# SOM_POWER.net
KiCad netlist of a schematic drawn in Altium Designer
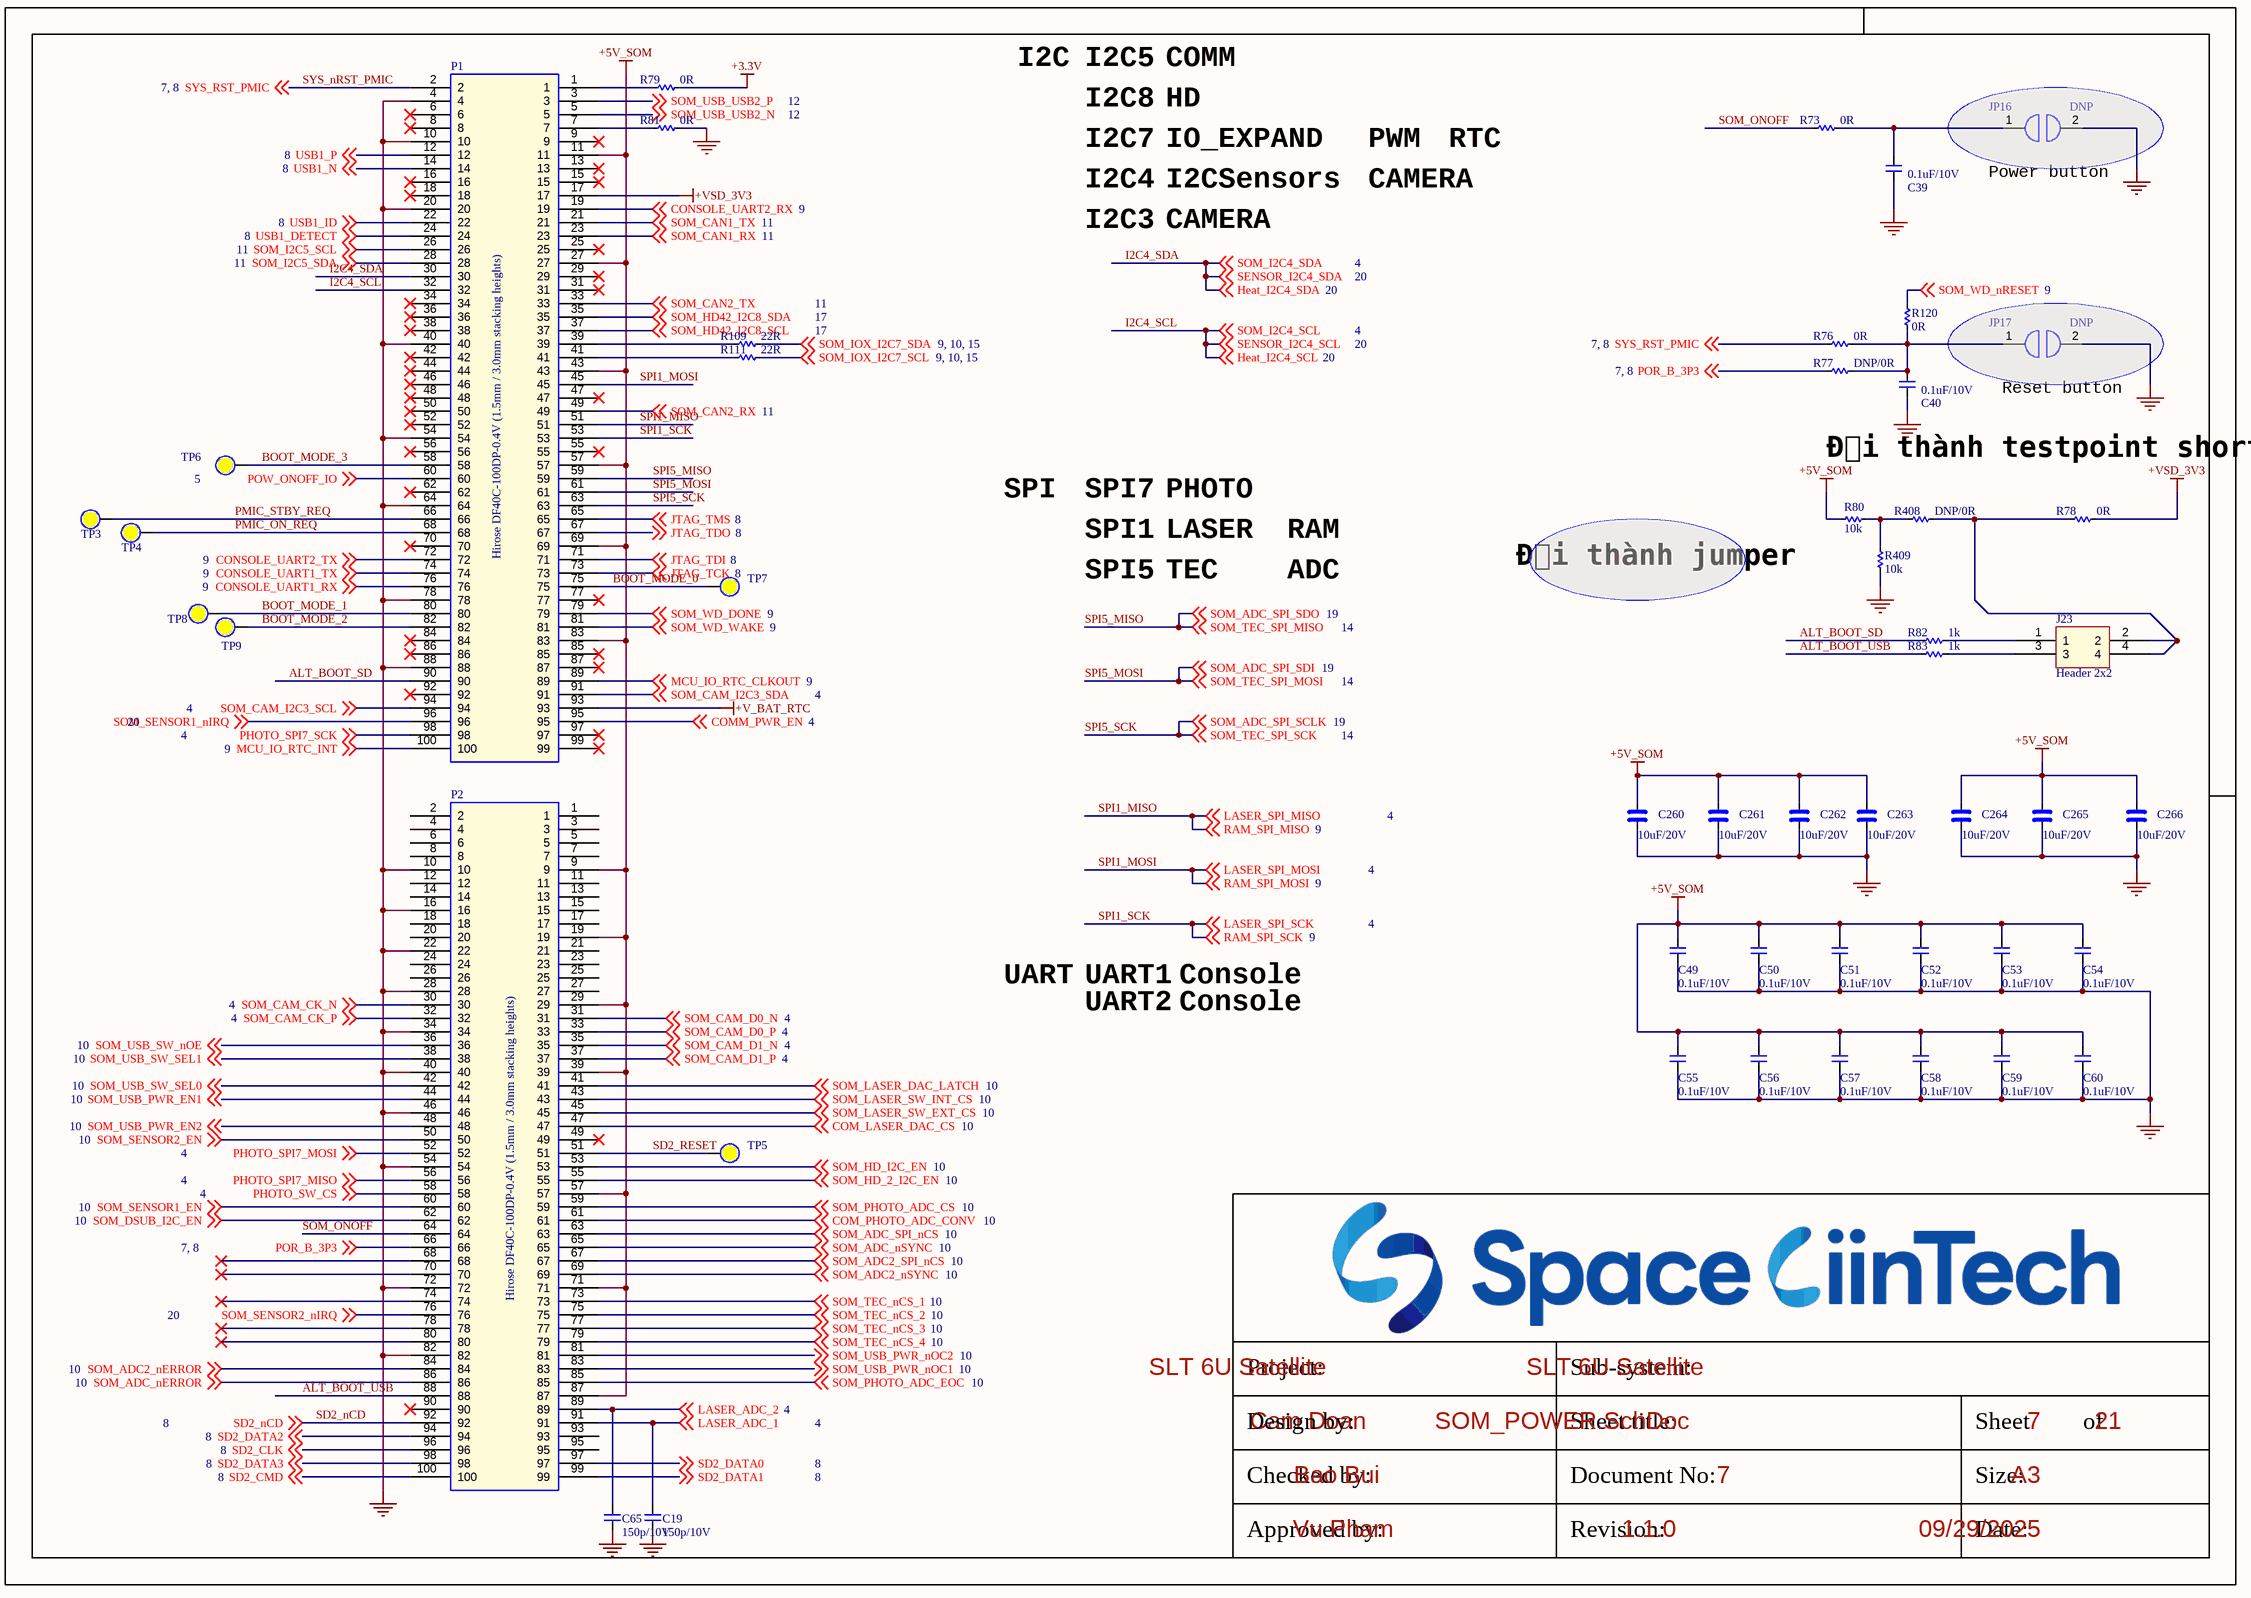
[diagram p0: SOM_POWER.SchDoc]

(export (version "E")
  (design (tool "Eeschema 10.0.6"))
  (components
    (comp (ref "C19")
      (value "150p/10V")
      (footprint "CAP_C_1005X60")
      (description "CAP CHIP")
      (libsource (lib "LABLIB") (part "_CAP_C_2"))
    )
    (comp (ref "C39")
      (value "0.1uF/10V")
      (footprint "CAP_C_1005X60")
      (description "CAP CHIP")
      (libsource (lib "LABLIB") (part "_CAP_C_2"))
    )
    (comp (ref "C40")
      (value "0.1uF/10V")
      (footprint "CAP_C_1005X60")
      (description "CAP CHIP")
      (libsource (lib "LABLIB") (part "_CAP_C_2"))
    )
    (comp (ref "C49")
      (value "0.1uF/10V")
      (footprint "CAP_C_1005X60")
      (description "CAP CHIP")
      (libsource (lib "LABLIB") (part "_CAP_C_2"))
    )
    (comp (ref "C50")
      (value "0.1uF/10V")
      (footprint "CAP_C_1005X60")
      (description "CAP CHIP")
      (libsource (lib "LABLIB") (part "_CAP_C_2"))
    )
    (comp (ref "C51")
      (value "0.1uF/10V")
      (footprint "CAP_C_1005X60")
      (description "CAP CHIP")
      (libsource (lib "LABLIB") (part "_CAP_C_2"))
    )
    (comp (ref "C52")
      (value "0.1uF/10V")
      (footprint "CAP_C_1005X60")
      (description "CAP CHIP")
      (libsource (lib "LABLIB") (part "_CAP_C_2"))
    )
    (comp (ref "C53")
      (value "0.1uF/10V")
      (footprint "CAP_C_1005X60")
      (description "CAP CHIP")
      (libsource (lib "LABLIB") (part "_CAP_C_2"))
    )
    (comp (ref "C54")
      (value "0.1uF/10V")
      (footprint "CAP_C_1005X60")
      (description "CAP CHIP")
      (libsource (lib "LABLIB") (part "_CAP_C_2"))
    )
    (comp (ref "C55")
      (value "0.1uF/10V")
      (footprint "CAP_C_1005X60")
      (description "CAP CHIP")
      (libsource (lib "LABLIB") (part "_CAP_C_2"))
    )
    (comp (ref "C56")
      (value "0.1uF/10V")
      (footprint "CAP_C_1005X60")
      (description "CAP CHIP")
      (libsource (lib "LABLIB") (part "_CAP_C_2"))
    )
    (comp (ref "C57")
      (value "0.1uF/10V")
      (footprint "CAP_C_1005X60")
      (description "CAP CHIP")
      (libsource (lib "LABLIB") (part "_CAP_C_2"))
    )
    (comp (ref "C58")
      (value "0.1uF/10V")
      (footprint "CAP_C_1005X60")
      (description "CAP CHIP")
      (libsource (lib "LABLIB") (part "_CAP_C_2"))
    )
    (comp (ref "C59")
      (value "0.1uF/10V")
      (footprint "CAP_C_1005X60")
      (description "CAP CHIP")
      (libsource (lib "LABLIB") (part "_CAP_C_2"))
    )
    (comp (ref "C60")
      (value "0.1uF/10V")
      (footprint "CAP_C_1005X60")
      (description "CAP CHIP")
      (libsource (lib "LABLIB") (part "_CAP_C_2"))
    )
    (comp (ref "C65")
      (value "150p/10V")
      (footprint "CAP_C_1005X60")
      (description "CAP CHIP")
      (libsource (lib "LABLIB") (part "_CAP_C_2"))
    )
    (comp (ref "C260")
      (value "10uF/20V")
      (footprint "CAP_C_2012X110")
      (description "CAP CHIP High Value")
      (libsource (lib "LABLIB") (part "_CAP_C_High_2"))
    )
    (comp (ref "C261")
      (value "10uF/20V")
      (footprint "CAP_C_2012X110")
      (description "CAP CHIP High Value")
      (libsource (lib "LABLIB") (part "_CAP_C_High_2"))
    )
    (comp (ref "C262")
      (value "10uF/20V")
      (footprint "CAP_C_2012X110")
      (description "CAP CHIP High Value")
      (libsource (lib "LABLIB") (part "_CAP_C_High_2"))
    )
    (comp (ref "C263")
      (value "10uF/20V")
      (footprint "CAP_C_2012X110")
      (description "CAP CHIP High Value")
      (libsource (lib "LABLIB") (part "_CAP_C_High_2"))
    )
    (comp (ref "C264")
      (value "10uF/20V")
      (footprint "CAP_C_2012X110")
      (description "CAP CHIP High Value")
      (libsource (lib "LABLIB") (part "_CAP_C_High_2"))
    )
    (comp (ref "C265")
      (value "10uF/20V")
      (footprint "CAP_C_2012X110")
      (description "CAP CHIP High Value")
      (libsource (lib "LABLIB") (part "_CAP_C_High_2"))
    )
    (comp (ref "C266")
      (value "10uF/20V")
      (footprint "CAP_C_2012X110")
      (description "CAP CHIP High Value")
      (libsource (lib "LABLIB") (part "_CAP_C_High_2"))
    )
    (comp (ref "J23")
      (value "Header 2x2")
      (footprint "CONN_54202-T0802ALF")
      (libsource (lib "LABLIB") (part "Header 2x2_Z"))
    )
    (comp (ref "JP16")
      (value "DNP")
      (footprint "TESTPOINT_SHORT_120X100_60")
      (libsource (lib "EXP_V1") (part "JUMPER"))
    )
    (comp (ref "JP17")
      (value "DNP")
      (footprint "TESTPOINT_SHORT_120X100_60")
      (libsource (lib "EXP_V1") (part "JUMPER"))
    )
    (comp (ref "P1")
      (value "Hirose DF40C-100DP-0.4V (1.5mm / 3.0mm stacking heights)")
      (footprint "B2B04M2X50R")
      (libsource (lib "*") (part "Hirose DF40C-100DP-0_0.4V"))
    )
    (comp (ref "P2")
      (value "Hirose DF40C-100DP-0.4V (1.5mm / 3.0mm stacking heights)")
      (footprint "B2B04M2X50R")
      (libsource (lib "*") (part "Hirose DF40C-100DP-0_1.4V"))
    )
    (comp (ref "R73")
      (value "0R")
      (footprint "RES_C_1005X40")
      (description "RES")
      (libsource (lib "LABLIB") (part "_RES_B_2"))
    )
    (comp (ref "R76")
      (value "0R")
      (footprint "RES_C_1005X40")
      (description "RES")
      (libsource (lib "LABLIB") (part "_RES_B_2"))
    )
    (comp (ref "R77")
      (value "DNP/0R")
      (footprint "RES_C_1005X40")
      (description "RES")
      (libsource (lib "LABLIB") (part "_RES_B_2"))
    )
    (comp (ref "R78")
      (value "0R")
      (footprint "RES_C_1005X40")
      (description "RES")
      (libsource (lib "LABLIB") (part "_RES_B_2"))
    )
    (comp (ref "R79")
      (value "0R")
      (footprint "RES_C_1005X40")
      (description "RES")
      (libsource (lib "LABLIB") (part "_RES_B_2"))
    )
    (comp (ref "R80")
      (value "10k")
      (footprint "RES_C_1005X40")
      (description "RES")
      (libsource (lib "LABLIB") (part "_RES_B_2"))
    )
    (comp (ref "R81")
      (value "0R")
      (footprint "RES_C_1005X40")
      (description "RES")
      (libsource (lib "LABLIB") (part "_RES_B_2"))
    )
    (comp (ref "R82")
      (value "1k")
      (footprint "RES_C_1005X40")
      (description "RES")
      (libsource (lib "LABLIB") (part "_RES_B_2"))
    )
    (comp (ref "R83")
      (value "1k")
      (footprint "RES_C_1005X40")
      (description "RES")
      (libsource (lib "LABLIB") (part "_RES_B_2"))
    )
    (comp (ref "R109")
      (value "22R")
      (footprint "RES_C_1005X40")
      (description "RES")
      (libsource (lib "LABLIB") (part "_RES_B_2"))
    )
    (comp (ref "R111")
      (value "22R")
      (footprint "RES_C_1005X40")
      (description "RES")
      (libsource (lib "LABLIB") (part "_RES_B_2"))
    )
    (comp (ref "R120")
      (value "0R")
      (footprint "RES_C_1005X40")
      (description "RES")
      (libsource (lib "LABLIB") (part "_RES_B_2"))
    )
    (comp (ref "R408")
      (value "DNP/0R")
      (footprint "RES_C_1005X40")
      (description "RES")
      (libsource (lib "LABLIB") (part "_RES_B_2"))
    )
    (comp (ref "R409")
      (value "10k")
      (footprint "RES_C_1005X40")
      (description "RES")
      (libsource (lib "LABLIB") (part "_RES_B_2"))
    )
    (comp (ref "TP3")
      (value "~")
      (footprint "Testpoint_TH_D130H80")
      (description "Test Point")
      (libsource (lib "") (part "Test Point_2"))
    )
    (comp (ref "TP4")
      (value "~")
      (footprint "Testpoint_TH_D130H80")
      (description "Test Point")
      (libsource (lib "") (part "Test Point_2"))
    )
    (comp (ref "TP5")
      (value "~")
      (footprint "Testpoint_TH_D130H80")
      (description "Test Point")
      (libsource (lib "LABLIB") (part "Test Point"))
    )
    (comp (ref "TP6")
      (value "~")
      (footprint "Testpoint_TH_D130H80")
      (description "Test Point")
      (libsource (lib "") (part "Test Point_1"))
    )
    (comp (ref "TP7")
      (value "~")
      (footprint "Testpoint_TH_D130H80")
      (description "Test Point")
      (libsource (lib "LABLIB") (part "Test Point"))
    )
    (comp (ref "TP8")
      (value "~")
      (footprint "Testpoint_TH_D130H80")
      (description "Test Point")
      (libsource (lib "") (part "Test Point_1"))
    )
    (comp (ref "TP9")
      (value "~")
      (footprint "Testpoint_TH_D130H80")
      (description "Test Point")
      (libsource (lib "") (part "Test Point_1"))
    )
  )
  (nets
    (net (code "1") (name "+3.3V") (class "Default")
      (node (ref "R79") (pin "1") (pinfunction "1_1") (pintype "passive"))
    )
    (net (code "2") (name "+5V_SOM") (class "Default")
      (node (ref "C260") (pin "1") (pinfunction "1_1") (pintype "passive"))
      (node (ref "C261") (pin "1") (pinfunction "1_1") (pintype "passive"))
      (node (ref "C262") (pin "1") (pinfunction "1_1") (pintype "passive"))
      (node (ref "C263") (pin "1") (pinfunction "1_1") (pintype "passive"))
      (node (ref "C264") (pin "1") (pinfunction "1_1") (pintype "passive"))
      (node (ref "C265") (pin "1") (pinfunction "1_1") (pintype "passive"))
      (node (ref "C266") (pin "1") (pinfunction "1_1") (pintype "passive"))
      (node (ref "C49") (pin "2") (pinfunction "2_2") (pintype "passive"))
      (node (ref "C50") (pin "2") (pinfunction "2_2") (pintype "passive"))
      (node (ref "C51") (pin "2") (pinfunction "2_2") (pintype "passive"))
      (node (ref "C52") (pin "2") (pinfunction "2_2") (pintype "passive"))
      (node (ref "C53") (pin "2") (pinfunction "2_2") (pintype "passive"))
      (node (ref "C54") (pin "2") (pinfunction "2_2") (pintype "passive"))
      (node (ref "C55") (pin "2") (pinfunction "2_2") (pintype "passive"))
      (node (ref "C56") (pin "2") (pinfunction "2_2") (pintype "passive"))
      (node (ref "C57") (pin "2") (pinfunction "2_2") (pintype "passive"))
      (node (ref "C58") (pin "2") (pinfunction "2_2") (pintype "passive"))
      (node (ref "C59") (pin "2") (pinfunction "2_2") (pintype "passive"))
      (node (ref "C60") (pin "2") (pinfunction "2_2") (pintype "passive"))
      (node (ref "P1") (pin "11") (pinfunction "11_11") (pintype "passive"))
      (node (ref "P1") (pin "27") (pinfunction "27_27") (pintype "passive"))
      (node (ref "P1") (pin "43") (pinfunction "43_43") (pintype "passive"))
      (node (ref "P1") (pin "57") (pinfunction "57_57") (pintype "passive"))
      (node (ref "P1") (pin "69") (pinfunction "69_69") (pintype "passive"))
      (node (ref "P1") (pin "83") (pinfunction "83_83") (pintype "passive"))
      (node (ref "P2") (pin "19") (pinfunction "19_19") (pintype "passive"))
      (node (ref "P2") (pin "29") (pinfunction "29_29") (pintype "passive"))
      (node (ref "P2") (pin "39") (pinfunction "39_39") (pintype "passive"))
      (node (ref "P2") (pin "57") (pinfunction "57_57") (pintype "passive"))
      (node (ref "P2") (pin "71") (pinfunction "71_71") (pintype "passive"))
      (node (ref "P2") (pin "87") (pinfunction "87_87") (pintype "passive"))
      (node (ref "P2") (pin "9") (pinfunction "9_9") (pintype "passive"))
      (node (ref "R80") (pin "1") (pinfunction "1_1") (pintype "passive"))
    )
    (net (code "3") (name "+VSD_3V3") (class "Default")
      (node (ref "P1") (pin "17") (pinfunction "17_17") (pintype "passive"))
      (node (ref "R78") (pin "1") (pinfunction "1_1") (pintype "passive"))
    )
    (net (code "4") (name "+V_BAT_RTC") (class "Default")
      (node (ref "P1") (pin "93") (pinfunction "93_93") (pintype "passive"))
    )
    (net (code "5") (name "/ALT_BOOT_SD") (class "Default")
      (node (ref "P1") (pin "90") (pinfunction "90_90") (pintype "passive"))
      (node (ref "R82") (pin "2") (pinfunction "2_2") (pintype "passive"))
    )
    (net (code "6") (name "/ALT_BOOT_USB") (class "Default")
      (node (ref "P2") (pin "88") (pinfunction "88_88") (pintype "passive"))
      (node (ref "R83") (pin "2") (pinfunction "2_2") (pintype "passive"))
    )
    (net (code "7") (name "/BOOT_MODE_0") (class "Default")
      (node (ref "P1") (pin "75") (pinfunction "75_75") (pintype "passive"))
      (node (ref "TP7") (pin "0") (pinfunction "0_0") (pintype "passive"))
    )
    (net (code "8") (name "/BOOT_MODE_1") (class "Default")
      (node (ref "P1") (pin "80") (pinfunction "80_80") (pintype "passive"))
      (node (ref "TP8") (pin "0") (pinfunction "0_0") (pintype "passive"))
    )
    (net (code "9") (name "/BOOT_MODE_2") (class "Default")
      (node (ref "P1") (pin "82") (pinfunction "82_82") (pintype "passive"))
      (node (ref "TP9") (pin "0") (pinfunction "0_0") (pintype "passive"))
    )
    (net (code "10") (name "/BOOT_MODE_3") (class "Default")
      (node (ref "P1") (pin "58") (pinfunction "58_58") (pintype "passive"))
      (node (ref "TP6") (pin "0") (pinfunction "0_0") (pintype "passive"))
    )
    (net (code "11") (name "/PMIC_ON_REQ") (class "Default")
      (node (ref "P1") (pin "68") (pinfunction "68_68") (pintype "passive"))
      (node (ref "TP4") (pin "0") (pinfunction "0_0") (pintype "passive"))
    )
    (net (code "12") (name "/PMIC_STBY_REQ") (class "Default")
      (node (ref "P1") (pin "66") (pinfunction "66_66") (pintype "passive"))
      (node (ref "TP3") (pin "0") (pinfunction "0_0") (pintype "passive"))
    )
    (net (code "13") (name "/SD2_RESET") (class "Default")
      (node (ref "P2") (pin "51") (pinfunction "51_51") (pintype "passive"))
      (node (ref "TP5") (pin "0") (pinfunction "0_0") (pintype "passive"))
    )
    (net (code "14") (name "/SOM_ONOFF") (class "Default")
      (node (ref "P2") (pin "64") (pinfunction "64_64") (pintype "passive"))
      (node (ref "R73") (pin "2") (pinfunction "2_2") (pintype "passive"))
    )
    (net (code "15") (name "COMM_PWR_EN") (class "Default")
      (node (ref "P1") (pin "95") (pinfunction "95_95") (pintype "passive"))
    )
    (net (code "16") (name "COM_LASER_DAC_CS") (class "Default")
      (node (ref "P2") (pin "47") (pinfunction "47_47") (pintype "passive"))
    )
    (net (code "17") (name "COM_PHOTO_ADC_CONV") (class "Default")
      (node (ref "P2") (pin "61") (pinfunction "61_61") (pintype "passive"))
    )
    (net (code "18") (name "CONSOLE_UART1_RX") (class "Default")
      (node (ref "P1") (pin "76") (pinfunction "76_76") (pintype "passive"))
    )
    (net (code "19") (name "CONSOLE_UART1_TX") (class "Default")
      (node (ref "P1") (pin "74") (pinfunction "74_74") (pintype "passive"))
    )
    (net (code "20") (name "CONSOLE_UART2_RX") (class "Default")
      (node (ref "P1") (pin "19") (pinfunction "19_19") (pintype "passive"))
    )
    (net (code "21") (name "CONSOLE_UART2_TX") (class "Default")
      (node (ref "P1") (pin "72") (pinfunction "72_72") (pintype "passive"))
    )
    (net (code "22") (name "GND") (class "Default")
      (node (ref "C19") (pin "2") (pinfunction "2_2") (pintype "passive"))
      (node (ref "C260") (pin "2") (pinfunction "2_2") (pintype "passive"))
      (node (ref "C261") (pin "2") (pinfunction "2_2") (pintype "passive"))
      (node (ref "C262") (pin "2") (pinfunction "2_2") (pintype "passive"))
      (node (ref "C263") (pin "2") (pinfunction "2_2") (pintype "passive"))
      (node (ref "C264") (pin "2") (pinfunction "2_2") (pintype "passive"))
      (node (ref "C265") (pin "2") (pinfunction "2_2") (pintype "passive"))
      (node (ref "C266") (pin "2") (pinfunction "2_2") (pintype "passive"))
      (node (ref "C39") (pin "1") (pinfunction "1_1") (pintype "passive"))
      (node (ref "C40") (pin "1") (pinfunction "1_1") (pintype "passive"))
      (node (ref "C49") (pin "1") (pinfunction "1_1") (pintype "passive"))
      (node (ref "C50") (pin "1") (pinfunction "1_1") (pintype "passive"))
      (node (ref "C51") (pin "1") (pinfunction "1_1") (pintype "passive"))
      (node (ref "C52") (pin "1") (pinfunction "1_1") (pintype "passive"))
      (node (ref "C53") (pin "1") (pinfunction "1_1") (pintype "passive"))
      (node (ref "C54") (pin "1") (pinfunction "1_1") (pintype "passive"))
      (node (ref "C55") (pin "1") (pinfunction "1_1") (pintype "passive"))
      (node (ref "C56") (pin "1") (pinfunction "1_1") (pintype "passive"))
      (node (ref "C57") (pin "1") (pinfunction "1_1") (pintype "passive"))
      (node (ref "C58") (pin "1") (pinfunction "1_1") (pintype "passive"))
      (node (ref "C59") (pin "1") (pinfunction "1_1") (pintype "passive"))
      (node (ref "C60") (pin "1") (pinfunction "1_1") (pintype "passive"))
      (node (ref "C65") (pin "2") (pinfunction "2_2") (pintype "passive"))
      (node (ref "JP16") (pin "2") (pinfunction "2_2") (pintype "passive"))
      (node (ref "JP17") (pin "2") (pinfunction "2_2") (pintype "passive"))
      (node (ref "P1") (pin "10") (pinfunction "10_10") (pintype "passive"))
      (node (ref "P1") (pin "20") (pinfunction "20_20") (pintype "passive"))
      (node (ref "P1") (pin "4") (pinfunction "4_4") (pintype "passive"))
      (node (ref "P1") (pin "40") (pinfunction "40_40") (pintype "passive"))
      (node (ref "P1") (pin "54") (pinfunction "54_54") (pintype "passive"))
      (node (ref "P1") (pin "64") (pinfunction "64_64") (pintype "passive"))
      (node (ref "P1") (pin "78") (pinfunction "78_78") (pintype "passive"))
      (node (ref "P1") (pin "88") (pinfunction "88_88") (pintype "passive"))
      (node (ref "P2") (pin "10") (pinfunction "10_10") (pintype "passive"))
      (node (ref "P2") (pin "16") (pinfunction "16_16") (pintype "passive"))
      (node (ref "P2") (pin "22") (pinfunction "22_22") (pintype "passive"))
      (node (ref "P2") (pin "28") (pinfunction "28_28") (pintype "passive"))
      (node (ref "P2") (pin "34") (pinfunction "34_34") (pintype "passive"))
      (node (ref "P2") (pin "40") (pinfunction "40_40") (pintype "passive"))
      (node (ref "P2") (pin "46") (pinfunction "46_46") (pintype "passive"))
      (node (ref "P2") (pin "54") (pinfunction "54_54") (pintype "passive"))
      (node (ref "P2") (pin "72") (pinfunction "72_72") (pintype "passive"))
      (node (ref "P2") (pin "82") (pinfunction "82_82") (pintype "passive"))
      (node (ref "R409") (pin "2") (pinfunction "2_2") (pintype "passive"))
      (node (ref "R81") (pin "1") (pinfunction "1_1") (pintype "passive"))
    )
    (net (code "23") (name "Heat_I2C4_SCL") (class "Default")
      (node (ref "P1") (pin "32") (pinfunction "32_32") (pintype "passive"))
    )
    (net (code "24") (name "Heat_I2C4_SDA") (class "Default")
      (node (ref "P1") (pin "30") (pinfunction "30_30") (pintype "passive"))
    )
    (net (code "25") (name "JTAG_TCK") (class "Default")
      (node (ref "P1") (pin "73") (pinfunction "73_73") (pintype "passive"))
    )
    (net (code "26") (name "JTAG_TDI") (class "Default")
      (node (ref "P1") (pin "71") (pinfunction "71_71") (pintype "passive"))
    )
    (net (code "27") (name "JTAG_TDO") (class "Default")
      (node (ref "P1") (pin "67") (pinfunction "67_67") (pintype "passive"))
    )
    (net (code "28") (name "JTAG_TMS") (class "Default")
      (node (ref "P1") (pin "65") (pinfunction "65_65") (pintype "passive"))
    )
    (net (code "29") (name "LASER_ADC_1") (class "Default")
      (node (ref "C19") (pin "1") (pinfunction "1_1") (pintype "passive"))
      (node (ref "P2") (pin "91") (pinfunction "91_91") (pintype "passive"))
    )
    (net (code "30") (name "LASER_ADC_2") (class "Default")
      (node (ref "C65") (pin "1") (pinfunction "1_1") (pintype "passive"))
      (node (ref "P2") (pin "89") (pinfunction "89_89") (pintype "passive"))
    )
    (net (code "31") (name "LASER_SPI_MISO") (class "Default")
      (node (ref "P1") (pin "51") (pinfunction "51_51") (pintype "passive"))
    )
    (net (code "32") (name "LASER_SPI_MOSI") (class "Default")
      (node (ref "P1") (pin "45") (pinfunction "45_45") (pintype "passive"))
    )
    (net (code "33") (name "LASER_SPI_SCK") (class "Default")
      (node (ref "P1") (pin "53") (pinfunction "53_53") (pintype "passive"))
    )
    (net (code "34") (name "MCU_IO_RTC_CLKOUT") (class "Default")
      (node (ref "P1") (pin "89") (pinfunction "89_89") (pintype "passive"))
    )
    (net (code "35") (name "MCU_IO_RTC_INT") (class "Default")
      (node (ref "P1") (pin "100") (pinfunction "100_100") (pintype "passive"))
    )
    (net (code "36") (name "Net-(C39-Pad2)") (class "Default")
      (node (ref "C39") (pin "2") (pinfunction "2_2") (pintype "passive"))
      (node (ref "JP16") (pin "1") (pinfunction "1_1") (pintype "passive"))
      (node (ref "R73") (pin "1") (pinfunction "1_1") (pintype "passive"))
    )
    (net (code "37") (name "Net-(C40-Pad2)") (class "Default")
      (node (ref "C40") (pin "2") (pinfunction "2_2") (pintype "passive"))
      (node (ref "JP17") (pin "1") (pinfunction "1_1") (pintype "passive"))
      (node (ref "R120") (pin "2") (pinfunction "2_2") (pintype "passive"))
      (node (ref "R76") (pin "1") (pinfunction "1_1") (pintype "passive"))
      (node (ref "R77") (pin "1") (pinfunction "1_1") (pintype "passive"))
    )
    (net (code "38") (name "Net-(J23-Pad1)") (class "Default")
      (node (ref "J23") (pin "1") (pinfunction "1_1") (pintype "passive"))
      (node (ref "R82") (pin "1") (pinfunction "1_1") (pintype "passive"))
    )
    (net (code "39") (name "Net-(J23-Pad2)") (class "Default")
      (node (ref "J23") (pin "2") (pinfunction "2_2") (pintype "passive"))
      (node (ref "J23") (pin "4") (pinfunction "4_4") (pintype "passive"))
      (node (ref "R408") (pin "1") (pinfunction "1_1") (pintype "passive"))
      (node (ref "R78") (pin "2") (pinfunction "2_2") (pintype "passive"))
    )
    (net (code "40") (name "Net-(J23-Pad3)") (class "Default")
      (node (ref "J23") (pin "3") (pinfunction "3_3") (pintype "passive"))
      (node (ref "R83") (pin "1") (pinfunction "1_1") (pintype "passive"))
    )
    (net (code "41") (name "Net-(P1-Pad1)") (class "Default")
      (node (ref "P1") (pin "1") (pinfunction "1_1") (pintype "passive"))
      (node (ref "R79") (pin "2") (pinfunction "2_2") (pintype "passive"))
    )
    (net (code "42") (name "Net-(P1-Pad7)") (class "Default")
      (node (ref "P1") (pin "7") (pinfunction "7_7") (pintype "passive"))
      (node (ref "R81") (pin "2") (pinfunction "2_2") (pintype "passive"))
    )
    (net (code "43") (name "Net-(P1-Pad39)") (class "Default")
      (node (ref "P1") (pin "39") (pinfunction "39_39") (pintype "passive"))
      (node (ref "R109") (pin "1") (pinfunction "1_1") (pintype "passive"))
    )
    (net (code "44") (name "Net-(P1-Pad41)") (class "Default")
      (node (ref "P1") (pin "41") (pinfunction "41_41") (pintype "passive"))
      (node (ref "R111") (pin "1") (pinfunction "1_1") (pintype "passive"))
    )
    (net (code "45") (name "Net-(R408-Pad2)") (class "Default")
      (node (ref "R408") (pin "2") (pinfunction "2_2") (pintype "passive"))
      (node (ref "R409") (pin "1") (pinfunction "1_1") (pintype "passive"))
      (node (ref "R80") (pin "2") (pinfunction "2_2") (pintype "passive"))
    )
    (net (code "46") (name "PHOTO_SPI7_MISO") (class "Default")
      (node (ref "P2") (pin "56") (pinfunction "56_56") (pintype "passive"))
    )
    (net (code "47") (name "PHOTO_SPI7_MOSI") (class "Default")
      (node (ref "P2") (pin "52") (pinfunction "52_52") (pintype "passive"))
    )
    (net (code "48") (name "PHOTO_SPI7_SCK") (class "Default")
      (node (ref "P1") (pin "98") (pinfunction "98_98") (pintype "passive"))
    )
    (net (code "49") (name "PHOTO_SW_CS") (class "Default")
      (node (ref "P2") (pin "58") (pinfunction "58_58") (pintype "passive"))
    )
    (net (code "50") (name "POR_B_3P3") (class "Default")
      (node (ref "P2") (pin "66") (pinfunction "66_66") (pintype "passive"))
      (node (ref "R77") (pin "2") (pinfunction "2_2") (pintype "passive"))
    )
    (net (code "51") (name "POW_ONOFF_IO") (class "Default")
      (node (ref "P1") (pin "60") (pinfunction "60_60") (pintype "passive"))
    )
    (net (code "52") (name "SD2_CLK") (class "Default")
      (node (ref "P2") (pin "96") (pinfunction "96_96") (pintype "passive"))
    )
    (net (code "53") (name "SD2_CMD") (class "Default")
      (node (ref "P2") (pin "100") (pinfunction "100_100") (pintype "passive"))
    )
    (net (code "54") (name "SD2_DATA0") (class "Default")
      (node (ref "P2") (pin "97") (pinfunction "97_97") (pintype "passive"))
    )
    (net (code "55") (name "SD2_DATA1") (class "Default")
      (node (ref "P2") (pin "99") (pinfunction "99_99") (pintype "passive"))
    )
    (net (code "56") (name "SD2_DATA2") (class "Default")
      (node (ref "P2") (pin "94") (pinfunction "94_94") (pintype "passive"))
    )
    (net (code "57") (name "SD2_DATA3") (class "Default")
      (node (ref "P2") (pin "98") (pinfunction "98_98") (pintype "passive"))
    )
    (net (code "58") (name "SD2_nCD") (class "Default")
      (node (ref "P2") (pin "92") (pinfunction "92_92") (pintype "passive"))
    )
    (net (code "59") (name "SOM_ADC2_SPI_nCS") (class "Default")
      (node (ref "P2") (pin "67") (pinfunction "67_67") (pintype "passive"))
    )
    (net (code "60") (name "SOM_ADC2_nERROR") (class "Default")
      (node (ref "P2") (pin "84") (pinfunction "84_84") (pintype "passive"))
    )
    (net (code "61") (name "SOM_ADC2_nSYNC") (class "Default")
      (node (ref "P2") (pin "69") (pinfunction "69_69") (pintype "passive"))
    )
    (net (code "62") (name "SOM_ADC_SPI_SCLK") (class "Default")
      (node (ref "P1") (pin "63") (pinfunction "63_63") (pintype "passive"))
    )
    (net (code "63") (name "SOM_ADC_SPI_SDI") (class "Default")
      (node (ref "P1") (pin "61") (pinfunction "61_61") (pintype "passive"))
    )
    (net (code "64") (name "SOM_ADC_SPI_SDO") (class "Default")
      (node (ref "P1") (pin "59") (pinfunction "59_59") (pintype "passive"))
    )
    (net (code "65") (name "SOM_ADC_SPI_nCS") (class "Default")
      (node (ref "P2") (pin "63") (pinfunction "63_63") (pintype "passive"))
    )
    (net (code "66") (name "SOM_ADC_nERROR") (class "Default")
      (node (ref "P2") (pin "86") (pinfunction "86_86") (pintype "passive"))
    )
    (net (code "67") (name "SOM_ADC_nSYNC") (class "Default")
      (node (ref "P2") (pin "65") (pinfunction "65_65") (pintype "passive"))
    )
    (net (code "68") (name "SOM_CAM_CK_N") (class "Default")
      (node (ref "P2") (pin "30") (pinfunction "30_30") (pintype "passive"))
    )
    (net (code "69") (name "SOM_CAM_CK_P") (class "Default")
      (node (ref "P2") (pin "32") (pinfunction "32_32") (pintype "passive"))
    )
    (net (code "70") (name "SOM_CAM_D0_N") (class "Default")
      (node (ref "P2") (pin "31") (pinfunction "31_31") (pintype "passive"))
    )
    (net (code "71") (name "SOM_CAM_D0_P") (class "Default")
      (node (ref "P2") (pin "33") (pinfunction "33_33") (pintype "passive"))
    )
    (net (code "72") (name "SOM_CAM_D1_N") (class "Default")
      (node (ref "P2") (pin "35") (pinfunction "35_35") (pintype "passive"))
    )
    (net (code "73") (name "SOM_CAM_D1_P") (class "Default")
      (node (ref "P2") (pin "37") (pinfunction "37_37") (pintype "passive"))
    )
    (net (code "74") (name "SOM_CAM_I2C3_SCL") (class "Default")
      (node (ref "P1") (pin "94") (pinfunction "94_94") (pintype "passive"))
    )
    (net (code "75") (name "SOM_CAM_I2C3_SDA") (class "Default")
      (node (ref "P1") (pin "91") (pinfunction "91_91") (pintype "passive"))
    )
    (net (code "76") (name "SOM_CAN1_RX") (class "Default")
      (node (ref "P1") (pin "23") (pinfunction "23_23") (pintype "passive"))
    )
    (net (code "77") (name "SOM_CAN1_TX") (class "Default")
      (node (ref "P1") (pin "21") (pinfunction "21_21") (pintype "passive"))
    )
    (net (code "78") (name "SOM_CAN2_RX") (class "Default")
      (node (ref "P1") (pin "49") (pinfunction "49_49") (pintype "passive"))
    )
    (net (code "79") (name "SOM_CAN2_TX") (class "Default")
      (node (ref "P1") (pin "33") (pinfunction "33_33") (pintype "passive"))
    )
    (net (code "80") (name "SOM_DSUB_I2C_EN") (class "Default")
      (node (ref "P2") (pin "62") (pinfunction "62_62") (pintype "passive"))
    )
    (net (code "81") (name "SOM_HD42_I2C8_SCL") (class "Default")
      (node (ref "P1") (pin "37") (pinfunction "37_37") (pintype "passive"))
    )
    (net (code "82") (name "SOM_HD42_I2C8_SDA") (class "Default")
      (node (ref "P1") (pin "35") (pinfunction "35_35") (pintype "passive"))
    )
    (net (code "83") (name "SOM_HD_2_I2C_EN") (class "Default")
      (node (ref "P2") (pin "55") (pinfunction "55_55") (pintype "passive"))
    )
    (net (code "84") (name "SOM_HD_I2C_EN") (class "Default")
      (node (ref "P2") (pin "53") (pinfunction "53_53") (pintype "passive"))
    )
    (net (code "85") (name "SOM_I2C5_SCL") (class "Default")
      (node (ref "P1") (pin "26") (pinfunction "26_26") (pintype "passive"))
    )
    (net (code "86") (name "SOM_I2C5_SDA") (class "Default")
      (node (ref "P1") (pin "28") (pinfunction "28_28") (pintype "passive"))
    )
    (net (code "87") (name "SOM_IOX_I2C7_SCL") (class "Default")
      (node (ref "R111") (pin "2") (pinfunction "2_2") (pintype "passive"))
    )
    (net (code "88") (name "SOM_IOX_I2C7_SDA") (class "Default")
      (node (ref "R109") (pin "2") (pinfunction "2_2") (pintype "passive"))
    )
    (net (code "89") (name "SOM_LASER_DAC_LATCH") (class "Default")
      (node (ref "P2") (pin "41") (pinfunction "41_41") (pintype "passive"))
    )
    (net (code "90") (name "SOM_LASER_SW_EXT_CS") (class "Default")
      (node (ref "P2") (pin "45") (pinfunction "45_45") (pintype "passive"))
    )
    (net (code "91") (name "SOM_LASER_SW_INT_CS") (class "Default")
      (node (ref "P2") (pin "43") (pinfunction "43_43") (pintype "passive"))
    )
    (net (code "92") (name "SOM_PHOTO_ADC_CS") (class "Default")
      (node (ref "P2") (pin "59") (pinfunction "59_59") (pintype "passive"))
    )
    (net (code "93") (name "SOM_PHOTO_ADC_EOC") (class "Default")
      (node (ref "P2") (pin "85") (pinfunction "85_85") (pintype "passive"))
    )
    (net (code "94") (name "SOM_SENSOR1_EN") (class "Default")
      (node (ref "P2") (pin "60") (pinfunction "60_60") (pintype "passive"))
    )
    (net (code "95") (name "SOM_SENSOR1_nIRQ") (class "Default")
      (node (ref "P1") (pin "96") (pinfunction "96_96") (pintype "passive"))
    )
    (net (code "96") (name "SOM_SENSOR2_EN") (class "Default")
      (node (ref "P2") (pin "50") (pinfunction "50_50") (pintype "passive"))
    )
    (net (code "97") (name "SOM_SENSOR2_nIRQ") (class "Default")
      (node (ref "P2") (pin "76") (pinfunction "76_76") (pintype "passive"))
    )
    (net (code "98") (name "SOM_TEC_nCS_1") (class "Default")
      (node (ref "P2") (pin "73") (pinfunction "73_73") (pintype "passive"))
    )
    (net (code "99") (name "SOM_TEC_nCS_2") (class "Default")
      (node (ref "P2") (pin "75") (pinfunction "75_75") (pintype "passive"))
    )
    (net (code "100") (name "SOM_TEC_nCS_3") (class "Default")
      (node (ref "P2") (pin "77") (pinfunction "77_77") (pintype "passive"))
    )
    (net (code "101") (name "SOM_TEC_nCS_4") (class "Default")
      (node (ref "P2") (pin "79") (pinfunction "79_79") (pintype "passive"))
    )
    (net (code "102") (name "SOM_USB_PWR_EN1") (class "Default")
      (node (ref "P2") (pin "44") (pinfunction "44_44") (pintype "passive"))
    )
    (net (code "103") (name "SOM_USB_PWR_EN2") (class "Default")
      (node (ref "P2") (pin "48") (pinfunction "48_48") (pintype "passive"))
    )
    (net (code "104") (name "SOM_USB_PWR_nOC1") (class "Default")
      (node (ref "P2") (pin "83") (pinfunction "83_83") (pintype "passive"))
    )
    (net (code "105") (name "SOM_USB_PWR_nOC2") (class "Default")
      (node (ref "P2") (pin "81") (pinfunction "81_81") (pintype "passive"))
    )
    (net (code "106") (name "SOM_USB_SW_SEL0") (class "Default")
      (node (ref "P2") (pin "42") (pinfunction "42_42") (pintype "passive"))
    )
    (net (code "107") (name "SOM_USB_SW_SEL1") (class "Default")
      (node (ref "P2") (pin "38") (pinfunction "38_38") (pintype "passive"))
    )
    (net (code "108") (name "SOM_USB_SW_nOE") (class "Default")
      (node (ref "P2") (pin "36") (pinfunction "36_36") (pintype "passive"))
    )
    (net (code "109") (name "SOM_USB_USB2_N") (class "Default")
      (node (ref "P1") (pin "5") (pinfunction "5_5") (pintype "passive"))
    )
    (net (code "110") (name "SOM_USB_USB2_P") (class "Default")
      (node (ref "P1") (pin "3") (pinfunction "3_3") (pintype "passive"))
    )
    (net (code "111") (name "SOM_WD_DONE") (class "Default")
      (node (ref "P1") (pin "79") (pinfunction "79_79") (pintype "passive"))
    )
    (net (code "112") (name "SOM_WD_WAKE") (class "Default")
      (node (ref "P1") (pin "81") (pinfunction "81_81") (pintype "passive"))
    )
    (net (code "113") (name "SOM_WD_nRESET") (class "Default")
      (node (ref "R120") (pin "1") (pinfunction "1_1") (pintype "passive"))
    )
    (net (code "114") (name "SYS_RST_PMIC") (class "Default")
      (node (ref "P1") (pin "2") (pinfunction "2_2") (pintype "passive"))
      (node (ref "R76") (pin "2") (pinfunction "2_2") (pintype "passive"))
    )
    (net (code "115") (name "USB1_DETECT") (class "Default")
      (node (ref "P1") (pin "24") (pinfunction "24_24") (pintype "passive"))
    )
    (net (code "116") (name "USB1_ID") (class "Default")
      (node (ref "P1") (pin "22") (pinfunction "22_22") (pintype "passive"))
    )
    (net (code "117") (name "USB1_N") (class "Default")
      (node (ref "P1") (pin "14") (pinfunction "14_14") (pintype "passive"))
    )
    (net (code "118") (name "USB1_P") (class "Default")
      (node (ref "P1") (pin "12") (pinfunction "12_12") (pintype "passive"))
    )
    (net (code "119") (name "unconnected-(P1-Pad6)") (class "Default")
      (node (ref "P1") (pin "6") (pinfunction "6_6") (pintype "passive+no_connect"))
    )
    (net (code "120") (name "unconnected-(P1-Pad8)") (class "Default")
      (node (ref "P1") (pin "8") (pinfunction "8_8") (pintype "passive+no_connect"))
    )
    (net (code "121") (name "unconnected-(P1-Pad9)") (class "Default")
      (node (ref "P1") (pin "9") (pinfunction "9_9") (pintype "passive+no_connect"))
    )
    (net (code "122") (name "unconnected-(P1-Pad13)") (class "Default")
      (node (ref "P1") (pin "13") (pinfunction "13_13") (pintype "passive+no_connect"))
    )
    (net (code "123") (name "unconnected-(P1-Pad15)") (class "Default")
      (node (ref "P1") (pin "15") (pinfunction "15_15") (pintype "passive+no_connect"))
    )
    (net (code "124") (name "unconnected-(P1-Pad16)") (class "Default")
      (node (ref "P1") (pin "16") (pinfunction "16_16") (pintype "passive+no_connect"))
    )
    (net (code "125") (name "unconnected-(P1-Pad18)") (class "Default")
      (node (ref "P1") (pin "18") (pinfunction "18_18") (pintype "passive+no_connect"))
    )
    (net (code "126") (name "unconnected-(P1-Pad25)") (class "Default")
      (node (ref "P1") (pin "25") (pinfunction "25_25") (pintype "passive+no_connect"))
    )
    (net (code "127") (name "unconnected-(P1-Pad29)") (class "Default")
      (node (ref "P1") (pin "29") (pinfunction "29_29") (pintype "passive+no_connect"))
    )
    (net (code "128") (name "unconnected-(P1-Pad31)") (class "Default")
      (node (ref "P1") (pin "31") (pinfunction "31_31") (pintype "passive+no_connect"))
    )
    (net (code "129") (name "unconnected-(P1-Pad34)") (class "Default")
      (node (ref "P1") (pin "34") (pinfunction "34_34") (pintype "passive+no_connect"))
    )
    (net (code "130") (name "unconnected-(P1-Pad36)") (class "Default")
      (node (ref "P1") (pin "36") (pinfunction "36_36") (pintype "passive+no_connect"))
    )
    (net (code "131") (name "unconnected-(P1-Pad38)") (class "Default")
      (node (ref "P1") (pin "38") (pinfunction "38_38") (pintype "passive+no_connect"))
    )
    (net (code "132") (name "unconnected-(P1-Pad42)") (class "Default")
      (node (ref "P1") (pin "42") (pinfunction "42_42") (pintype "passive+no_connect"))
    )
    (net (code "133") (name "unconnected-(P1-Pad44)") (class "Default")
      (node (ref "P1") (pin "44") (pinfunction "44_44") (pintype "passive+no_connect"))
    )
    (net (code "134") (name "unconnected-(P1-Pad46)") (class "Default")
      (node (ref "P1") (pin "46") (pinfunction "46_46") (pintype "passive+no_connect"))
    )
    (net (code "135") (name "unconnected-(P1-Pad47)") (class "Default")
      (node (ref "P1") (pin "47") (pinfunction "47_47") (pintype "passive+no_connect"))
    )
    (net (code "136") (name "unconnected-(P1-Pad48)") (class "Default")
      (node (ref "P1") (pin "48") (pinfunction "48_48") (pintype "passive+no_connect"))
    )
    (net (code "137") (name "unconnected-(P1-Pad50)") (class "Default")
      (node (ref "P1") (pin "50") (pinfunction "50_50") (pintype "passive+no_connect"))
    )
    (net (code "138") (name "unconnected-(P1-Pad52)") (class "Default")
      (node (ref "P1") (pin "52") (pinfunction "52_52") (pintype "passive+no_connect"))
    )
    (net (code "139") (name "unconnected-(P1-Pad55)") (class "Default")
      (node (ref "P1") (pin "55") (pinfunction "55_55") (pintype "passive+no_connect"))
    )
    (net (code "140") (name "unconnected-(P1-Pad56)") (class "Default")
      (node (ref "P1") (pin "56") (pinfunction "56_56") (pintype "passive+no_connect"))
    )
    (net (code "141") (name "unconnected-(P1-Pad62)") (class "Default")
      (node (ref "P1") (pin "62") (pinfunction "62_62") (pintype "passive+no_connect"))
    )
    (net (code "142") (name "unconnected-(P1-Pad70)") (class "Default")
      (node (ref "P1") (pin "70") (pinfunction "70_70") (pintype "passive+no_connect"))
    )
    (net (code "143") (name "unconnected-(P1-Pad77)") (class "Default")
      (node (ref "P1") (pin "77") (pinfunction "77_77") (pintype "passive+no_connect"))
    )
    (net (code "144") (name "unconnected-(P1-Pad84)") (class "Default")
      (node (ref "P1") (pin "84") (pinfunction "84_84") (pintype "passive+no_connect"))
    )
    (net (code "145") (name "unconnected-(P1-Pad85)") (class "Default")
      (node (ref "P1") (pin "85") (pinfunction "85_85") (pintype "passive+no_connect"))
    )
    (net (code "146") (name "unconnected-(P1-Pad86)") (class "Default")
      (node (ref "P1") (pin "86") (pinfunction "86_86") (pintype "passive+no_connect"))
    )
    (net (code "147") (name "unconnected-(P1-Pad87)") (class "Default")
      (node (ref "P1") (pin "87") (pinfunction "87_87") (pintype "passive+no_connect"))
    )
    (net (code "148") (name "unconnected-(P1-Pad92)") (class "Default")
      (node (ref "P1") (pin "92") (pinfunction "92_92") (pintype "passive+no_connect"))
    )
    (net (code "149") (name "unconnected-(P1-Pad97)") (class "Default")
      (node (ref "P1") (pin "97") (pinfunction "97_97") (pintype "passive+no_connect"))
    )
    (net (code "150") (name "unconnected-(P1-Pad99)") (class "Default")
      (node (ref "P1") (pin "99") (pinfunction "99_99") (pintype "passive+no_connect"))
    )
    (net (code "151") (name "unconnected-(P2-Pad1)") (class "Default")
      (node (ref "P2") (pin "1") (pinfunction "1_1") (pintype "passive"))
    )
    (net (code "152") (name "unconnected-(P2-Pad2)") (class "Default")
      (node (ref "P2") (pin "2") (pinfunction "2_2") (pintype "passive"))
    )
    (net (code "153") (name "unconnected-(P2-Pad3)") (class "Default")
      (node (ref "P2") (pin "3") (pinfunction "3_3") (pintype "passive"))
    )
    (net (code "154") (name "unconnected-(P2-Pad4)") (class "Default")
      (node (ref "P2") (pin "4") (pinfunction "4_4") (pintype "passive"))
    )
    (net (code "155") (name "unconnected-(P2-Pad5)") (class "Default")
      (node (ref "P2") (pin "5") (pinfunction "5_5") (pintype "passive"))
    )
    (net (code "156") (name "unconnected-(P2-Pad6)") (class "Default")
      (node (ref "P2") (pin "6") (pinfunction "6_6") (pintype "passive"))
    )
    (net (code "157") (name "unconnected-(P2-Pad7)") (class "Default")
      (node (ref "P2") (pin "7") (pinfunction "7_7") (pintype "passive"))
    )
    (net (code "158") (name "unconnected-(P2-Pad8)") (class "Default")
      (node (ref "P2") (pin "8") (pinfunction "8_8") (pintype "passive"))
    )
    (net (code "159") (name "unconnected-(P2-Pad11)") (class "Default")
      (node (ref "P2") (pin "11") (pinfunction "11_11") (pintype "passive"))
    )
    (net (code "160") (name "unconnected-(P2-Pad12)") (class "Default")
      (node (ref "P2") (pin "12") (pinfunction "12_12") (pintype "passive"))
    )
    (net (code "161") (name "unconnected-(P2-Pad13)") (class "Default")
      (node (ref "P2") (pin "13") (pinfunction "13_13") (pintype "passive"))
    )
    (net (code "162") (name "unconnected-(P2-Pad14)") (class "Default")
      (node (ref "P2") (pin "14") (pinfunction "14_14") (pintype "passive"))
    )
    (net (code "163") (name "unconnected-(P2-Pad15)") (class "Default")
      (node (ref "P2") (pin "15") (pinfunction "15_15") (pintype "passive"))
    )
    (net (code "164") (name "unconnected-(P2-Pad17)") (class "Default")
      (node (ref "P2") (pin "17") (pinfunction "17_17") (pintype "passive"))
    )
    (net (code "165") (name "unconnected-(P2-Pad18)") (class "Default")
      (node (ref "P2") (pin "18") (pinfunction "18_18") (pintype "passive"))
    )
    (net (code "166") (name "unconnected-(P2-Pad20)") (class "Default")
      (node (ref "P2") (pin "20") (pinfunction "20_20") (pintype "passive"))
    )
    (net (code "167") (name "unconnected-(P2-Pad21)") (class "Default")
      (node (ref "P2") (pin "21") (pinfunction "21_21") (pintype "passive"))
    )
    (net (code "168") (name "unconnected-(P2-Pad23)") (class "Default")
      (node (ref "P2") (pin "23") (pinfunction "23_23") (pintype "passive"))
    )
    (net (code "169") (name "unconnected-(P2-Pad24)") (class "Default")
      (node (ref "P2") (pin "24") (pinfunction "24_24") (pintype "passive"))
    )
    (net (code "170") (name "unconnected-(P2-Pad25)") (class "Default")
      (node (ref "P2") (pin "25") (pinfunction "25_25") (pintype "passive"))
    )
    (net (code "171") (name "unconnected-(P2-Pad26)") (class "Default")
      (node (ref "P2") (pin "26") (pinfunction "26_26") (pintype "passive"))
    )
    (net (code "172") (name "unconnected-(P2-Pad27)") (class "Default")
      (node (ref "P2") (pin "27") (pinfunction "27_27") (pintype "passive"))
    )
    (net (code "173") (name "unconnected-(P2-Pad49)") (class "Default")
      (node (ref "P2") (pin "49") (pinfunction "49_49") (pintype "passive+no_connect"))
    )
    (net (code "174") (name "unconnected-(P2-Pad68)") (class "Default")
      (node (ref "P2") (pin "68") (pinfunction "68_68") (pintype "passive+no_connect"))
    )
    (net (code "175") (name "unconnected-(P2-Pad70)") (class "Default")
      (node (ref "P2") (pin "70") (pinfunction "70_70") (pintype "passive+no_connect"))
    )
    (net (code "176") (name "unconnected-(P2-Pad74)") (class "Default")
      (node (ref "P2") (pin "74") (pinfunction "74_74") (pintype "passive+no_connect"))
    )
    (net (code "177") (name "unconnected-(P2-Pad78)") (class "Default")
      (node (ref "P2") (pin "78") (pinfunction "78_78") (pintype "passive+no_connect"))
    )
    (net (code "178") (name "unconnected-(P2-Pad80)") (class "Default")
      (node (ref "P2") (pin "80") (pinfunction "80_80") (pintype "passive+no_connect"))
    )
    (net (code "179") (name "unconnected-(P2-Pad90)") (class "Default")
      (node (ref "P2") (pin "90") (pinfunction "90_90") (pintype "passive+no_connect"))
    )
    (net (code "180") (name "unconnected-(P2-Pad93)") (class "Default")
      (node (ref "P2") (pin "93") (pinfunction "93_93") (pintype "passive"))
    )
    (net (code "181") (name "unconnected-(P2-Pad95)") (class "Default")
      (node (ref "P2") (pin "95") (pinfunction "95_95") (pintype "passive"))
    )
  )
)
